# SparkFun_ESP8266_Thing_v10.net
KiCad netlist of a schematic drawn in EAGLE
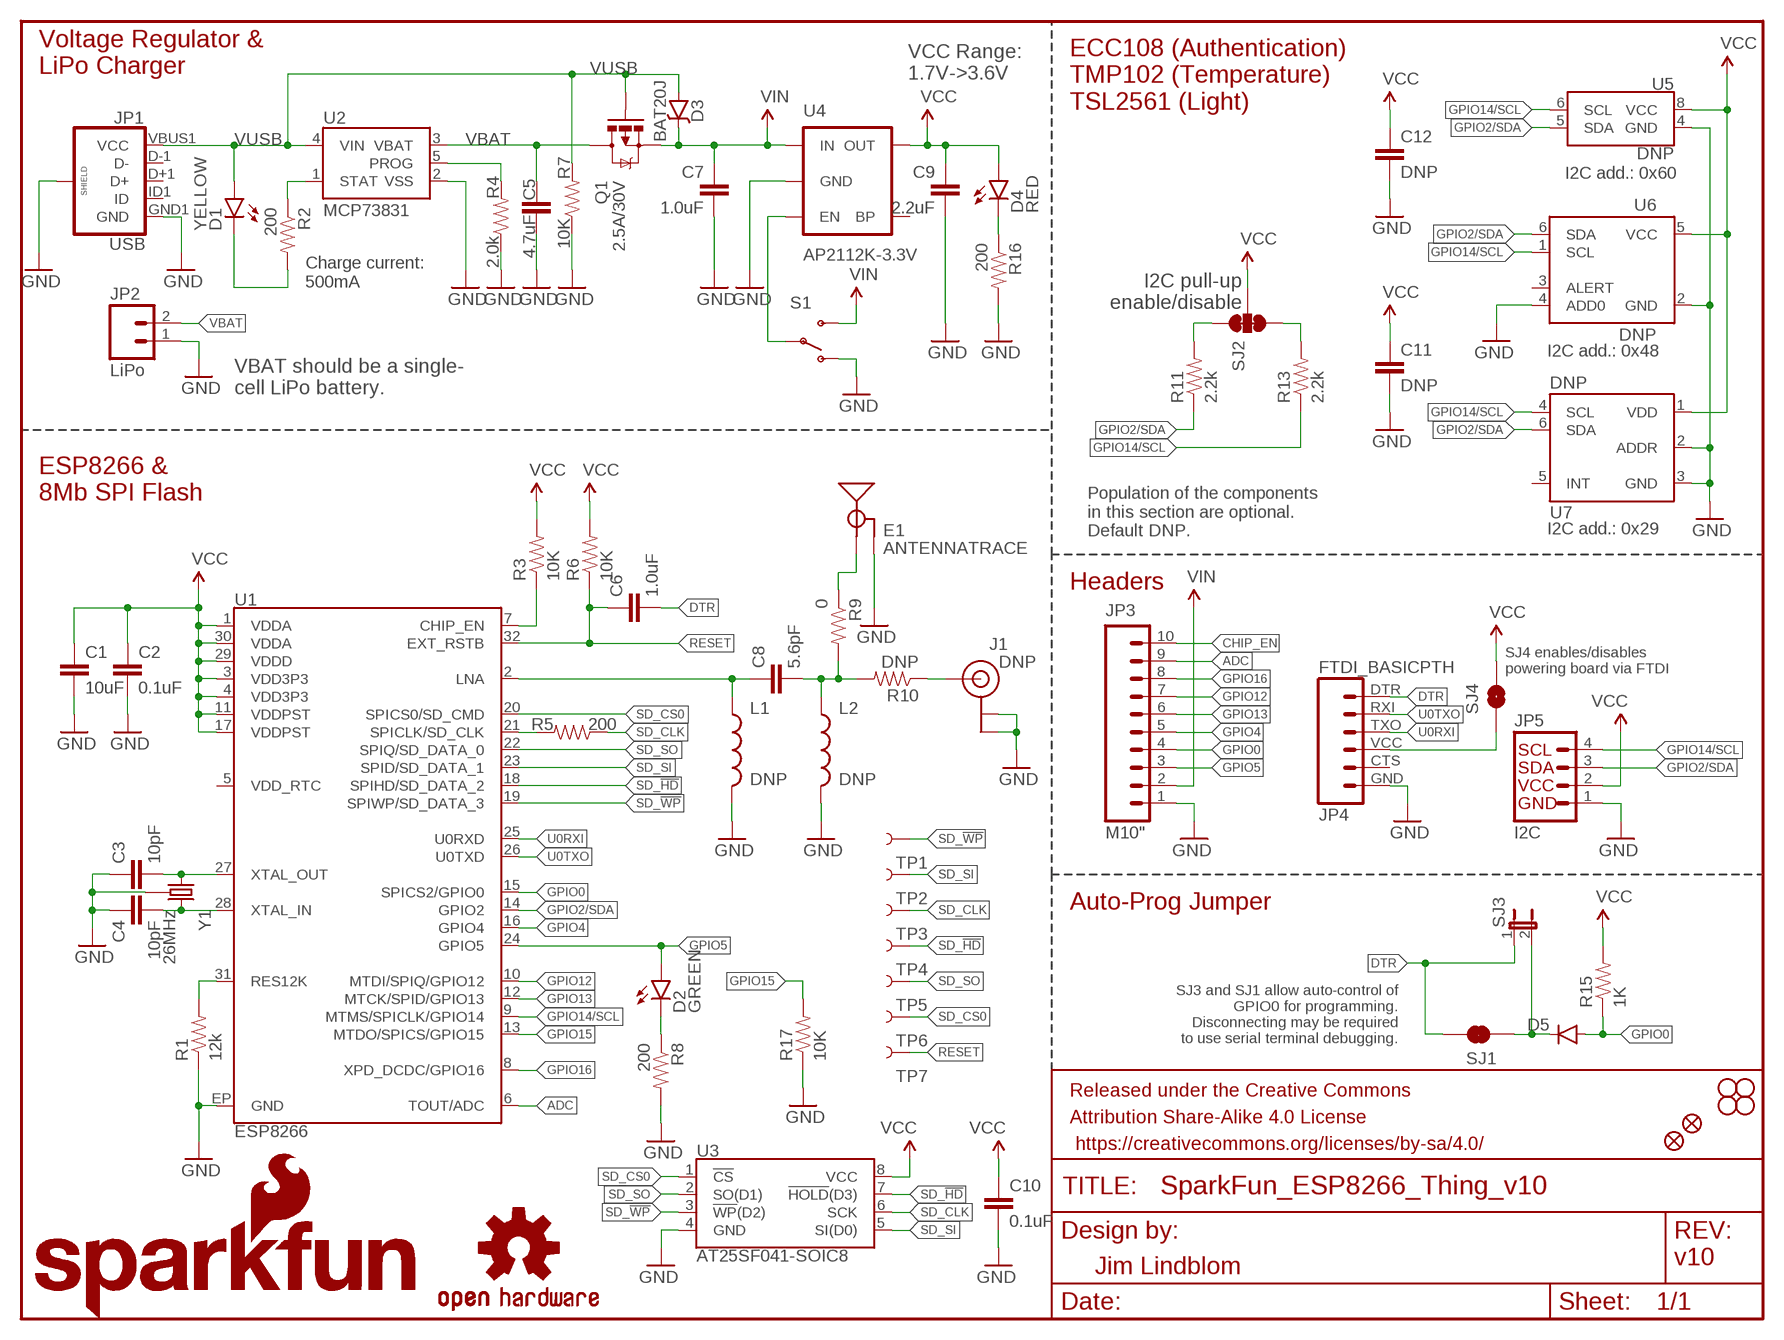
[diagram p0: schematic, sheet 1]

(export (version "E")
  (design (tool "Eeschema 10.0.6"))
  (components
    (comp (ref "C1")
      (value "10uF")
      (footprint "eagle-import:0603-CAP")
      (libsource (lib "eagle-import") (part "10UF-6.3V-20%(0603)"))
    )
    (comp (ref "C2")
      (value "0.1uF")
      (footprint "eagle-import:0603-CAP")
      (libsource (lib "eagle-import") (part "0.1UF-25V(+80/-20%)(0603)"))
    )
    (comp (ref "C3")
      (value "10pF")
      (footprint "eagle-import:0603-CAP")
      (libsource (lib "eagle-import") (part "10PF-50V-5%(0603)"))
    )
    (comp (ref "C4")
      (value "10pF")
      (footprint "eagle-import:0603-CAP")
      (libsource (lib "eagle-import") (part "10PF-50V-5%(0603)"))
    )
    (comp (ref "C5")
      (value "4.7uF")
      (footprint "eagle-import:0603-CAP")
      (libsource (lib "eagle-import") (part "4.7UF-6.3V-10%(0603)0603"))
    )
    (comp (ref "C6")
      (value "1.0uF")
      (footprint "eagle-import:0603-CAP")
      (libsource (lib "eagle-import") (part "1.0UF-16V-10%(0603)"))
    )
    (comp (ref "C7")
      (value "1.0uF")
      (footprint "eagle-import:0805")
      (libsource (lib "eagle-import") (part "1.0UF-25V-+80/-20(0805)"))
    )
    (comp (ref "C8")
      (value "5.6pF")
      (footprint "eagle-import:0603-CAP")
      (libsource (lib "eagle-import") (part "CAP0603-CAP"))
    )
    (comp (ref "C9")
      (value "2.2uF")
      (footprint "eagle-import:0603-CAP")
      (libsource (lib "eagle-import") (part "2.2UF-10V-20%(0603)"))
    )
    (comp (ref "C10")
      (value "0.1uF")
      (footprint "eagle-import:0603-CAP")
      (libsource (lib "eagle-import") (part "0.1UF-25V(+80/-20%)(0603)"))
    )
    (comp (ref "C11")
      (value "DNP")
      (footprint "eagle-import:0603-CAP")
      (libsource (lib "eagle-import") (part "0.1UF-25V(+80/-20%)(0603)"))
    )
    (comp (ref "C12")
      (value "DNP")
      (footprint "eagle-import:0603-CAP")
      (libsource (lib "eagle-import") (part "0.1UF-25V(+80/-20%)(0603)"))
    )
    (comp (ref "D1")
      (value "YELLOW")
      (footprint "eagle-import:LED-0603")
      (libsource (lib "eagle-import") (part "LED-YELLOW0603"))
    )
    (comp (ref "D2")
      (value "GREEN")
      (footprint "eagle-import:LED-0603")
      (libsource (lib "eagle-import") (part "LED-GREEN0603"))
    )
    (comp (ref "D3")
      (value "BAT20J")
      (footprint "eagle-import:SOD-323")
      (libsource (lib "eagle-import") (part "DIODE-SCHOTTKY-BAT20J"))
    )
    (comp (ref "D4")
      (value "RED")
      (footprint "eagle-import:LED-0603")
      (libsource (lib "eagle-import") (part "LED-RED0603"))
    )
    (comp (ref "D5")
      (value "DIODEBAS16")
      (footprint "eagle-import:SOD-323")
      (libsource (lib "eagle-import") (part "DIODEBAS16"))
    )
    (comp (ref "E1")
      (value "ANTENNATRACE")
      (footprint "eagle-import:TRACE_ANTENNA_2.4GHZ_25.7MM")
      (libsource (lib "eagle-import") (part "ANTENNATRACE"))
    )
    (comp (ref "FID1")
      (value "FIDUCIAL1X2")
      (footprint "eagle-import:FIDUCIAL-1X2")
      (libsource (lib "eagle-import") (part "FIDUCIAL1X2"))
    )
    (comp (ref "FID2")
      (value "FIDUCIAL1X2")
      (footprint "eagle-import:FIDUCIAL-1X2")
      (libsource (lib "eagle-import") (part "FIDUCIAL1X2"))
    )
    (comp (ref "FRAME1")
      (value "FRAME-LETTER")
      (footprint "eagle-import:CREATIVE_COMMONS")
      (libsource (lib "eagle-import") (part "FRAME-LETTER"))
    )
    (comp (ref "J1")
      (value "DNP")
      (footprint "eagle-import:U.FL")
      (libsource (lib "eagle-import") (part "U.FL"))
    )
    (comp (ref "JP1")
      (value "USB")
      (footprint "eagle-import:USB-B-MICRO-SMD_V03")
      (libsource (lib "eagle-import") (part "USB_MICROB_PLUGCONN-11752"))
    )
    (comp (ref "JP2")
      (value "LiPo")
      (footprint "eagle-import:JST-2-PTH")
      (libsource (lib "eagle-import") (part "M02JST-PTH-2"))
    )
    (comp (ref "JP3")
      (value "M10\"")
      (footprint "eagle-import:1X10")
      (libsource (lib "eagle-import") (part "M10{dblquote}"))
    )
    (comp (ref "JP4")
      (value "FTDI_BASICPTH")
      (footprint "eagle-import:FTDI_BASIC")
      (libsource (lib "eagle-import") (part "FTDI_BASICPTH"))
    )
    (comp (ref "JP5")
      (value "I2C")
      (footprint "eagle-import:1X04")
      (libsource (lib "eagle-import") (part "I2C_STANDARD"))
    )
    (comp (ref "L1")
      (value "DNP")
      (footprint "eagle-import:0603")
      (libsource (lib "eagle-import") (part "INDUCTOR0603"))
    )
    (comp (ref "L2")
      (value "DNP")
      (footprint "eagle-import:0603")
      (libsource (lib "eagle-import") (part "INDUCTOR0603"))
    )
    (comp (ref "LOGO1")
      (value "SFE_LOGO_NAME.2_INCH")
      (footprint "eagle-import:SFE_LOGO_NAME_.2")
      (libsource (lib "eagle-import") (part "SFE_LOGO_NAME.2_INCH"))
    )
    (comp (ref "LOGO3")
      (value "SFE_LOGO_FLAME.1_INCH")
      (footprint "eagle-import:SFE_LOGO_FLAME_.1")
      (libsource (lib "eagle-import") (part "SFE_LOGO_FLAME.1_INCH"))
    )
    (comp (ref "LOGO4")
      (value "OSHW-LOGOS")
      (footprint "eagle-import:OSHW-LOGO-S")
      (libsource (lib "eagle-import") (part "OSHW-LOGOS"))
    )
    (comp (ref "Q1")
      (value "2.5A/30V")
      (footprint "eagle-import:SOT23-3")
      (libsource (lib "eagle-import") (part "MOSFET-PCHANNELDMG2307L"))
    )
    (comp (ref "R1")
      (value "12k")
      (footprint "eagle-import:0603-RES")
      (libsource (lib "eagle-import") (part "12KOHM-1/10W-1%(0603)"))
    )
    (comp (ref "R2")
      (value "200")
      (footprint "eagle-import:0603-RES")
      (libsource (lib "eagle-import") (part "200OHM1/10W1%(0603)"))
    )
    (comp (ref "R3")
      (value "10K")
      (footprint "eagle-import:0603-RES")
      (libsource (lib "eagle-import") (part "10KOHM1/10W1%(0603)0603"))
    )
    (comp (ref "R4")
      (value "2.0k")
      (footprint "eagle-import:0603-RES")
      (libsource (lib "eagle-import") (part "2.0KOHM1/10W5%(0603)"))
    )
    (comp (ref "R5")
      (value "200")
      (footprint "eagle-import:0603-RES")
      (libsource (lib "eagle-import") (part "200OHM1/10W1%(0603)"))
    )
    (comp (ref "R6")
      (value "10K")
      (footprint "eagle-import:0603-RES")
      (libsource (lib "eagle-import") (part "10KOHM1/10W1%(0603)0603"))
    )
    (comp (ref "R7")
      (value "10K")
      (footprint "eagle-import:0603-RES")
      (libsource (lib "eagle-import") (part "10KOHM1/10W1%(0603)0603"))
    )
    (comp (ref "R8")
      (value "200")
      (footprint "eagle-import:0603-RES")
      (libsource (lib "eagle-import") (part "200OHM1/10W1%(0603)"))
    )
    (comp (ref "R9")
      (value "0")
      (footprint "eagle-import:0603")
      (libsource (lib "eagle-import") (part "0OHM1/10W5%(0603)"))
    )
    (comp (ref "R10")
      (value "DNP")
      (footprint "eagle-import:0603-RES")
      (libsource (lib "eagle-import") (part "RESISTOR0603-RES"))
    )
    (comp (ref "R11")
      (value "2.2k")
      (footprint "eagle-import:0603-RES")
      (libsource (lib "eagle-import") (part "2.2KOHM1/10W1%(0603)"))
    )
    (comp (ref "R13")
      (value "2.2k")
      (footprint "eagle-import:0603-RES")
      (libsource (lib "eagle-import") (part "2.2KOHM1/10W1%(0603)"))
    )
    (comp (ref "R15")
      (value "1K")
      (footprint "eagle-import:0603-RES")
      (libsource (lib "eagle-import") (part "1KOHM1/10W1%(0603)"))
    )
    (comp (ref "R16")
      (value "200")
      (footprint "eagle-import:0603-RES")
      (libsource (lib "eagle-import") (part "200OHM1/10W1%(0603)"))
    )
    (comp (ref "R17")
      (value "10K")
      (footprint "eagle-import:0603-RES")
      (libsource (lib "eagle-import") (part "10KOHM1/10W1%(0603)0603"))
    )
    (comp (ref "S1")
      (value "SWITCH-SPDT-SMD-A")
      (footprint "eagle-import:SWITCH-SPST-SMD-A")
      (libsource (lib "eagle-import") (part "SWITCH-SPDT-SMD-A"))
    )
    (comp (ref "SJ1")
      (value "JUMPER-PAD-2-NC_BY_TRACE")
      (footprint "eagle-import:PAD-JUMPER-2-NC_BY_TRACE_YES_SILK")
      (libsource (lib "eagle-import") (part "JUMPER-PAD-2-NC_BY_TRACE"))
    )
    (comp (ref "SJ2")
      (value "JUMPER-PAD-3-NC_BY_TRACE")
      (footprint "eagle-import:PAD-JUMPER-3-3OF3_NC_BY_TRACE_YES_SILK_FULL_BOX")
      (libsource (lib "eagle-import") (part "JUMPER-PAD-3-NC_BY_TRACE"))
    )
    (comp (ref "SJ3")
      (value "JUMPER-PTH-2-NC")
      (footprint "eagle-import:PTH-JUMPER-NC_BOTTOM_NO_SILK")
      (libsource (lib "eagle-import") (part "JUMPER-PTH-2-NC"))
    )
    (comp (ref "SJ4")
      (value "JUMPER-PAD-2-NOYES_SILK")
      (footprint "eagle-import:PAD-JUMPER-2-NO_YES_SILK")
      (libsource (lib "eagle-import") (part "JUMPER-PAD-2-NOYES_SILK"))
    )
    (comp (ref "STANDOFF1")
      (value "STAND-OFF")
      (footprint "eagle-import:STAND-OFF")
      (libsource (lib "eagle-import") (part "STAND-OFF"))
    )
    (comp (ref "STANDOFF2")
      (value "STAND-OFF")
      (footprint "eagle-import:STAND-OFF")
      (libsource (lib "eagle-import") (part "STAND-OFF"))
    )
    (comp (ref "STANDOFF3")
      (value "STAND-OFF")
      (footprint "eagle-import:STAND-OFF")
      (libsource (lib "eagle-import") (part "STAND-OFF"))
    )
    (comp (ref "STANDOFF4")
      (value "STAND-OFF")
      (footprint "eagle-import:STAND-OFF")
      (libsource (lib "eagle-import") (part "STAND-OFF"))
    )
    (comp (ref "TP1")
      (value "TEST-POINT3X5")
      (footprint "eagle-import:PAD.03X.05")
      (libsource (lib "eagle-import") (part "TEST-POINT3X5"))
    )
    (comp (ref "TP2")
      (value "TEST-POINT3X5")
      (footprint "eagle-import:PAD.03X.05")
      (libsource (lib "eagle-import") (part "TEST-POINT3X5"))
    )
    (comp (ref "TP3")
      (value "TEST-POINT3X5")
      (footprint "eagle-import:PAD.03X.05")
      (libsource (lib "eagle-import") (part "TEST-POINT3X5"))
    )
    (comp (ref "TP4")
      (value "TEST-POINT3X5")
      (footprint "eagle-import:PAD.03X.05")
      (libsource (lib "eagle-import") (part "TEST-POINT3X5"))
    )
    (comp (ref "TP5")
      (value "TEST-POINT3X5")
      (footprint "eagle-import:PAD.03X.05")
      (libsource (lib "eagle-import") (part "TEST-POINT3X5"))
    )
    (comp (ref "TP6")
      (value "TEST-POINT3X5")
      (footprint "eagle-import:PAD.03X.05")
      (libsource (lib "eagle-import") (part "TEST-POINT3X5"))
    )
    (comp (ref "TP7")
      (value "TEST-POINT3X5")
      (footprint "eagle-import:PAD.03X.05")
      (libsource (lib "eagle-import") (part "TEST-POINT3X5"))
    )
    (comp (ref "U1")
      (value "ESP8266")
      (footprint "eagle-import:QFN32")
      (libsource (lib "eagle-import") (part "ESP8266"))
    )
    (comp (ref "U2")
      (value "MCP73831")
      (footprint "eagle-import:SOT23-5")
      (libsource (lib "eagle-import") (part "MCP73831"))
    )
    (comp (ref "U3")
      (value "AT25SF041-SOIC8")
      (footprint "eagle-import:SO08")
      (libsource (lib "eagle-import") (part "AT25SF041-SOIC8"))
    )
    (comp (ref "U4")
      (value "AP2112K-3.3V")
      (footprint "eagle-import:SOT23-5")
      (libsource (lib "eagle-import") (part "V_REG_LDOSMD"))
    )
    (comp (ref "U5")
      (value "DNP")
      (footprint "eagle-import:UDFN8")
      (libsource (lib "eagle-import") (part "ATECC108-MAHDA"))
    )
    (comp (ref "U6")
      (value "DNP")
      (footprint "eagle-import:SOT563-2")
      (libsource (lib "eagle-import") (part "TMP1021{colon}1"))
    )
    (comp (ref "U7")
      (value "DNP")
      (footprint "eagle-import:FN-6")
      (libsource (lib "eagle-import") (part "TSL2561FN"))
    )
    (comp (ref "Y1")
      (value "26MHz")
      (footprint "eagle-import:CRYSTAL-SMD-3.2X2.5")
      (libsource (lib "eagle-import") (part "CRYSTAL-GROUNDED3.2X2.5"))
    )
  )
  (nets
    (net (code "1") (name "/SD_~{HD}") (class "Default")
      (node (ref "TP4") (pin "P$1") (pinfunction "1_P$1") (pintype "bidirectional"))
      (node (ref "U1") (pin "18") (pinfunction "SPIHD/SD_DATA_2_18") (pintype "bidirectional"))
      (node (ref "U3") (pin "7") (pinfunction "~{HOLD}(D3)_7") (pintype "bidirectional"))
    )
    (net (code "2") (name "/SD_~{WP}") (class "Default")
      (node (ref "TP1") (pin "P$1") (pinfunction "1_P$1") (pintype "bidirectional"))
      (node (ref "U1") (pin "19") (pinfunction "SPIWP/SD_DATA_3_19") (pintype "bidirectional"))
      (node (ref "U3") (pin "3") (pinfunction "~{WP}(D2)_3") (pintype "bidirectional"))
    )
    (net (code "3") (name "/VUSB") (class "Default")
      (node (ref "D1") (pin "A") (pinfunction "A_A") (pintype "passive"))
      (node (ref "D3") (pin "A") (pinfunction "A_A") (pintype "passive"))
      (node (ref "JP1") (pin "VBUS1") (pinfunction "VCC_VBUS1") (pintype "bidirectional"))
      (node (ref "Q1") (pin "1") (pinfunction "G_1") (pintype "passive"))
      (node (ref "R7") (pin "2") (pinfunction "2_2") (pintype "passive"))
      (node (ref "U2") (pin "4") (pinfunction "VIN_4") (pintype "power_in"))
    )
    (net (code "4") (name "ADC") (class "Default")
      (node (ref "JP3") (pin "9") (pinfunction "9_9") (pintype "passive"))
      (node (ref "U1") (pin "6") (pinfunction "TOUT/ADC_6") (pintype "bidirectional"))
    )
    (net (code "5") (name "CHIP_EN") (class "Default")
      (node (ref "JP3") (pin "10") (pinfunction "10_10") (pintype "passive"))
      (node (ref "R3") (pin "1") (pinfunction "1_1") (pintype "passive"))
      (node (ref "U1") (pin "7") (pinfunction "CHIP_EN_7") (pintype "bidirectional"))
    )
    (net (code "6") (name "DTR") (class "Default")
      (node (ref "C6") (pin "2") (pinfunction "2_2") (pintype "passive"))
      (node (ref "JP4") (pin "DTR") (pinfunction "1_DTR") (pintype "passive"))
      (node (ref "SJ1") (pin "2") (pinfunction "2_2") (pintype "passive"))
      (node (ref "SJ3") (pin "1") (pinfunction "1_1") (pintype "passive"))
    )
    (net (code "7") (name "GND") (class "Default")
      (node (ref "C1") (pin "2") (pinfunction "2_2") (pintype "passive"))
      (node (ref "C10") (pin "2") (pinfunction "2_2") (pintype "passive"))
      (node (ref "C11") (pin "2") (pinfunction "2_2") (pintype "passive"))
      (node (ref "C12") (pin "2") (pinfunction "2_2") (pintype "passive"))
      (node (ref "C2") (pin "2") (pinfunction "2_2") (pintype "passive"))
      (node (ref "C3") (pin "1") (pinfunction "1_1") (pintype "passive"))
      (node (ref "C4") (pin "1") (pinfunction "1_1") (pintype "passive"))
      (node (ref "C5") (pin "2") (pinfunction "2_2") (pintype "passive"))
      (node (ref "C7") (pin "2") (pinfunction "2_2") (pintype "passive"))
      (node (ref "C9") (pin "2") (pinfunction "2_2") (pintype "passive"))
      (node (ref "E1") (pin "GND") (pinfunction "GND_GND") (pintype "bidirectional"))
      (node (ref "E1") (pin "GND2") (pinfunction "GND_GND2") (pintype "bidirectional"))
      (node (ref "J1") (pin "P$1") (pinfunction "GND_P$1") (pintype "bidirectional"))
      (node (ref "J1") (pin "P$2") (pinfunction "GND_P$2") (pintype "bidirectional"))
      (node (ref "JP1") (pin "GND1") (pinfunction "GND_GND1") (pintype "bidirectional"))
      (node (ref "JP1") (pin "SHIELD1") (pinfunction "SHIELD_SHIELD1") (pintype "bidirectional"))
      (node (ref "JP1") (pin "SHIELD2") (pinfunction "SHIELD_SHIELD2") (pintype "bidirectional"))
      (node (ref "JP1") (pin "SHIELD3") (pinfunction "SHIELD_SHIELD3") (pintype "bidirectional"))
      (node (ref "JP2") (pin "1") (pinfunction "1_1") (pintype "passive"))
      (node (ref "JP3") (pin "1") (pinfunction "1_1") (pintype "passive"))
      (node (ref "JP4") (pin "GND") (pinfunction "6_GND") (pintype "passive"))
      (node (ref "JP5") (pin "1") (pinfunction "1_1") (pintype "passive"))
      (node (ref "L1") (pin "2") (pinfunction "2_2") (pintype "passive"))
      (node (ref "L2") (pin "2") (pinfunction "2_2") (pintype "passive"))
      (node (ref "R1") (pin "1") (pinfunction "1_1") (pintype "passive"))
      (node (ref "R16") (pin "2") (pinfunction "2_2") (pintype "passive"))
      (node (ref "R17") (pin "1") (pinfunction "1_1") (pintype "passive"))
      (node (ref "R4") (pin "1") (pinfunction "1_1") (pintype "passive"))
      (node (ref "R7") (pin "1") (pinfunction "1_1") (pintype "passive"))
      (node (ref "R8") (pin "2") (pinfunction "2_2") (pintype "passive"))
      (node (ref "S1") (pin "1") (pinfunction "O_1") (pintype "passive"))
      (node (ref "U1") (pin "EP") (pinfunction "GND_EP") (pintype "bidirectional"))
      (node (ref "U2") (pin "2") (pinfunction "VSS_2") (pintype "power_in"))
      (node (ref "U3") (pin "4") (pinfunction "GND_4") (pintype "bidirectional"))
      (node (ref "U4") (pin "2") (pinfunction "GND_2") (pintype "input"))
      (node (ref "U5") (pin "4") (pinfunction "GND_4") (pintype "bidirectional"))
      (node (ref "U6") (pin "2") (pinfunction "GND_2") (pintype "bidirectional"))
      (node (ref "U6") (pin "4") (pinfunction "ADD0_4") (pintype "bidirectional"))
      (node (ref "U7") (pin "2") (pinfunction "ADDR_2") (pintype "input"))
      (node (ref "U7") (pin "3") (pinfunction "GND_3") (pintype "power_in"))
      (node (ref "Y1") (pin "2") (pinfunction "GND_2") (pintype "passive"))
      (node (ref "Y1") (pin "4") (pinfunction "GND_4") (pintype "passive"))
    )
    (net (code "8") (name "GPIO0") (class "Default")
      (node (ref "D5") (pin "A") (pinfunction "A_A") (pintype "passive"))
      (node (ref "JP3") (pin "4") (pinfunction "4_4") (pintype "passive"))
      (node (ref "R15") (pin "1") (pinfunction "1_1") (pintype "passive"))
      (node (ref "U1") (pin "15") (pinfunction "SPICS2/GPIO0_15") (pintype "bidirectional"))
    )
    (net (code "9") (name "GPIO2{slash}SDA") (class "Default")
      (node (ref "JP5") (pin "3") (pinfunction "3_3") (pintype "passive"))
      (node (ref "R11") (pin "1") (pinfunction "1_1") (pintype "passive"))
      (node (ref "U1") (pin "14") (pinfunction "GPIO2_14") (pintype "bidirectional"))
      (node (ref "U5") (pin "5") (pinfunction "SDA_5") (pintype "bidirectional"))
      (node (ref "U6") (pin "6") (pinfunction "SDA_6") (pintype "bidirectional"))
      (node (ref "U7") (pin "6") (pinfunction "SDA_6") (pintype "bidirectional"))
    )
    (net (code "10") (name "GPIO4") (class "Default")
      (node (ref "JP3") (pin "5") (pinfunction "5_5") (pintype "passive"))
      (node (ref "U1") (pin "16") (pinfunction "GPIO4_16") (pintype "bidirectional"))
    )
    (net (code "11") (name "GPIO5") (class "Default")
      (node (ref "D2") (pin "A") (pinfunction "A_A") (pintype "passive"))
      (node (ref "JP3") (pin "3") (pinfunction "3_3") (pintype "passive"))
      (node (ref "U1") (pin "24") (pinfunction "GPIO5_24") (pintype "bidirectional"))
    )
    (net (code "12") (name "GPIO12") (class "Default")
      (node (ref "JP3") (pin "7") (pinfunction "7_7") (pintype "passive"))
      (node (ref "U1") (pin "10") (pinfunction "MTDI/SPIQ/GPIO12_10") (pintype "bidirectional"))
    )
    (net (code "13") (name "GPIO13") (class "Default")
      (node (ref "JP3") (pin "6") (pinfunction "6_6") (pintype "passive"))
      (node (ref "U1") (pin "12") (pinfunction "MTCK/SPID/GPIO13_12") (pintype "bidirectional"))
    )
    (net (code "14") (name "GPIO14{slash}SCL") (class "Default")
      (node (ref "JP5") (pin "4") (pinfunction "4_4") (pintype "passive"))
      (node (ref "R13") (pin "1") (pinfunction "1_1") (pintype "passive"))
      (node (ref "U1") (pin "9") (pinfunction "MTMS/SPICLK/GPIO14_9") (pintype "bidirectional"))
      (node (ref "U5") (pin "6") (pinfunction "SCL_6") (pintype "bidirectional"))
      (node (ref "U6") (pin "1") (pinfunction "SCL_1") (pintype "bidirectional"))
      (node (ref "U7") (pin "4") (pinfunction "SCL_4") (pintype "input"))
    )
    (net (code "15") (name "GPIO15") (class "Default")
      (node (ref "R17") (pin "2") (pinfunction "2_2") (pintype "passive"))
      (node (ref "U1") (pin "13") (pinfunction "MTDO/SPICS/GPIO15_13") (pintype "bidirectional"))
    )
    (net (code "16") (name "GPIO16") (class "Default")
      (node (ref "JP3") (pin "8") (pinfunction "8_8") (pintype "passive"))
      (node (ref "U1") (pin "8") (pinfunction "XPD_DCDC/GPIO16_8") (pintype "bidirectional"))
    )
    (net (code "17") (name "Net-(C8-Pad2)") (class "Default")
      (node (ref "C8") (pin "2") (pinfunction "2_2") (pintype "passive"))
      (node (ref "L2") (pin "1") (pinfunction "1_1") (pintype "passive"))
      (node (ref "R10") (pin "2") (pinfunction "2_2") (pintype "passive"))
      (node (ref "R9") (pin "2") (pinfunction "2_2") (pintype "passive"))
    )
    (net (code "18") (name "Net-(D1-PadC)") (class "Default")
      (node (ref "D1") (pin "C") (pinfunction "C_C") (pintype "passive"))
      (node (ref "R2") (pin "2") (pinfunction "2_2") (pintype "passive"))
    )
    (net (code "19") (name "Net-(D2-PadC)") (class "Default")
      (node (ref "D2") (pin "C") (pinfunction "C_C") (pintype "passive"))
      (node (ref "R8") (pin "1") (pinfunction "1_1") (pintype "passive"))
    )
    (net (code "20") (name "Net-(D4-PadC)") (class "Default")
      (node (ref "D4") (pin "C") (pinfunction "C_C") (pintype "passive"))
      (node (ref "R16") (pin "1") (pinfunction "1_1") (pintype "passive"))
    )
    (net (code "21") (name "Net-(D5-PadC)") (class "Default")
      (node (ref "D5") (pin "C") (pinfunction "C_C") (pintype "passive"))
      (node (ref "SJ1") (pin "1") (pinfunction "1_1") (pintype "passive"))
      (node (ref "SJ3") (pin "2") (pinfunction "2_2") (pintype "passive"))
    )
    (net (code "22") (name "Net-(E1-SIGNAL)") (class "Default")
      (node (ref "E1") (pin "ANT") (pinfunction "SIGNAL_ANT") (pintype "bidirectional"))
      (node (ref "R9") (pin "1") (pinfunction "1_1") (pintype "passive"))
    )
    (net (code "23") (name "Net-(J1-SIGNAL)") (class "Default")
      (node (ref "J1") (pin "P$3") (pinfunction "SIGNAL_P$3") (pintype "bidirectional"))
      (node (ref "R10") (pin "1") (pinfunction "1_1") (pintype "passive"))
    )
    (net (code "24") (name "Net-(JP4-4)") (class "Default")
      (node (ref "JP4") (pin "VCC") (pinfunction "4_VCC") (pintype "passive"))
      (node (ref "SJ4") (pin "1") (pinfunction "1_1") (pintype "passive"))
    )
    (net (code "25") (name "Net-(R11-Pad2)") (class "Default")
      (node (ref "R11") (pin "2") (pinfunction "2_2") (pintype "passive"))
      (node (ref "SJ2") (pin "1") (pinfunction "1_1") (pintype "passive"))
    )
    (net (code "26") (name "Net-(R13-Pad2)") (class "Default")
      (node (ref "R13") (pin "2") (pinfunction "2_2") (pintype "passive"))
      (node (ref "SJ2") (pin "3") (pinfunction "3_3") (pintype "passive"))
    )
    (net (code "27") (name "Net-(S1-P)") (class "Default")
      (node (ref "S1") (pin "2") (pinfunction "P_2") (pintype "passive"))
      (node (ref "U4") (pin "3") (pinfunction "EN_3") (pintype "input"))
    )
    (net (code "28") (name "Net-(U1-LNA)") (class "Default")
      (node (ref "C8") (pin "1") (pinfunction "1_1") (pintype "passive"))
      (node (ref "L1") (pin "1") (pinfunction "1_1") (pintype "passive"))
      (node (ref "U1") (pin "2") (pinfunction "LNA_2") (pintype "bidirectional"))
    )
    (net (code "29") (name "Net-(U1-RES12K)") (class "Default")
      (node (ref "R1") (pin "2") (pinfunction "2_2") (pintype "passive"))
      (node (ref "U1") (pin "31") (pinfunction "RES12K_31") (pintype "bidirectional"))
    )
    (net (code "30") (name "Net-(U1-SPICLK{slash}SD_CLK)") (class "Default")
      (node (ref "R5") (pin "2") (pinfunction "2_2") (pintype "passive"))
      (node (ref "U1") (pin "21") (pinfunction "SPICLK/SD_CLK_21") (pintype "bidirectional"))
    )
    (net (code "31") (name "Net-(U1-XTAL_IN)") (class "Default")
      (node (ref "C4") (pin "2") (pinfunction "2_2") (pintype "passive"))
      (node (ref "U1") (pin "28") (pinfunction "XTAL_IN_28") (pintype "bidirectional"))
      (node (ref "Y1") (pin "3") (pinfunction "2_3") (pintype "passive"))
    )
    (net (code "32") (name "Net-(U1-XTAL_OUT)") (class "Default")
      (node (ref "C3") (pin "2") (pinfunction "2_2") (pintype "passive"))
      (node (ref "U1") (pin "27") (pinfunction "XTAL_OUT_27") (pintype "bidirectional"))
      (node (ref "Y1") (pin "1") (pinfunction "1_1") (pintype "passive"))
    )
    (net (code "33") (name "Net-(U2-PROG)") (class "Default")
      (node (ref "R4") (pin "2") (pinfunction "2_2") (pintype "passive"))
      (node (ref "U2") (pin "5") (pinfunction "PROG_5") (pintype "input"))
    )
    (net (code "34") (name "Net-(U2-STAT)") (class "Default")
      (node (ref "R2") (pin "1") (pinfunction "1_1") (pintype "passive"))
      (node (ref "U2") (pin "1") (pinfunction "STAT_1") (pintype "output"))
    )
    (net (code "35") (name "RESET") (class "Default")
      (node (ref "C6") (pin "1") (pinfunction "1_1") (pintype "passive"))
      (node (ref "R6") (pin "1") (pinfunction "1_1") (pintype "passive"))
      (node (ref "TP7") (pin "P$1") (pinfunction "1_P$1") (pintype "bidirectional"))
      (node (ref "U1") (pin "32") (pinfunction "EXT_RSTB_32") (pintype "bidirectional"))
    )
    (net (code "36") (name "SD_CLK") (class "Default")
      (node (ref "R5") (pin "1") (pinfunction "1_1") (pintype "passive"))
      (node (ref "TP3") (pin "P$1") (pinfunction "1_P$1") (pintype "bidirectional"))
      (node (ref "U3") (pin "6") (pinfunction "SCK_6") (pintype "bidirectional"))
    )
    (net (code "37") (name "SD_CS0") (class "Default")
      (node (ref "TP6") (pin "P$1") (pinfunction "1_P$1") (pintype "bidirectional"))
      (node (ref "U1") (pin "20") (pinfunction "SPICS0/SD_CMD_20") (pintype "bidirectional"))
      (node (ref "U3") (pin "1") (pinfunction "~{CS}_1") (pintype "bidirectional"))
    )
    (net (code "38") (name "SD_SI") (class "Default")
      (node (ref "TP2") (pin "P$1") (pinfunction "1_P$1") (pintype "bidirectional"))
      (node (ref "U1") (pin "23") (pinfunction "SPID/SD_DATA_1_23") (pintype "bidirectional"))
      (node (ref "U3") (pin "5") (pinfunction "SI(D0)_5") (pintype "bidirectional"))
    )
    (net (code "39") (name "SD_SO") (class "Default")
      (node (ref "TP5") (pin "P$1") (pinfunction "1_P$1") (pintype "bidirectional"))
      (node (ref "U1") (pin "22") (pinfunction "SPIQ/SD_DATA_0_22") (pintype "bidirectional"))
      (node (ref "U3") (pin "2") (pinfunction "SO(D1)_2") (pintype "bidirectional"))
    )
    (net (code "40") (name "U0RXI") (class "Default")
      (node (ref "JP4") (pin "TXO") (pinfunction "3_TXO") (pintype "passive"))
      (node (ref "U1") (pin "25") (pinfunction "U0RXD_25") (pintype "bidirectional"))
    )
    (net (code "41") (name "U0TXO") (class "Default")
      (node (ref "JP4") (pin "RXI") (pinfunction "2_RXI") (pintype "passive"))
      (node (ref "U1") (pin "26") (pinfunction "U0TXD_26") (pintype "bidirectional"))
    )
    (net (code "42") (name "VBAT") (class "Default")
      (node (ref "C5") (pin "1") (pinfunction "1_1") (pintype "passive"))
      (node (ref "JP2") (pin "2") (pinfunction "2_2") (pintype "passive"))
      (node (ref "Q1") (pin "3") (pinfunction "D_3") (pintype "passive"))
      (node (ref "U2") (pin "3") (pinfunction "VBAT_3") (pintype "power_in"))
    )
    (net (code "43") (name "VCC") (class "Default")
      (node (ref "C1") (pin "1") (pinfunction "1_1") (pintype "passive"))
      (node (ref "C10") (pin "1") (pinfunction "1_1") (pintype "passive"))
      (node (ref "C11") (pin "1") (pinfunction "1_1") (pintype "passive"))
      (node (ref "C12") (pin "1") (pinfunction "1_1") (pintype "passive"))
      (node (ref "C2") (pin "1") (pinfunction "1_1") (pintype "passive"))
      (node (ref "C9") (pin "1") (pinfunction "1_1") (pintype "passive"))
      (node (ref "D4") (pin "A") (pinfunction "A_A") (pintype "passive"))
      (node (ref "JP5") (pin "2") (pinfunction "2_2") (pintype "passive"))
      (node (ref "R15") (pin "2") (pinfunction "2_2") (pintype "passive"))
      (node (ref "R3") (pin "2") (pinfunction "2_2") (pintype "passive"))
      (node (ref "R6") (pin "2") (pinfunction "2_2") (pintype "passive"))
      (node (ref "SJ2") (pin "2") (pinfunction "2_2") (pintype "passive"))
      (node (ref "SJ4") (pin "2") (pinfunction "2_2") (pintype "passive"))
      (node (ref "U1") (pin "1") (pinfunction "VDDA_1") (pintype "bidirectional"))
      (node (ref "U1") (pin "11") (pinfunction "VDDPST_11") (pintype "bidirectional"))
      (node (ref "U1") (pin "17") (pinfunction "VDDPST_17") (pintype "bidirectional"))
      (node (ref "U1") (pin "29") (pinfunction "VDDD_29") (pintype "bidirectional"))
      (node (ref "U1") (pin "3") (pinfunction "VDD3P3_3") (pintype "bidirectional"))
      (node (ref "U1") (pin "30") (pinfunction "VDDA_30") (pintype "bidirectional"))
      (node (ref "U1") (pin "4") (pinfunction "VDD3P3_4") (pintype "bidirectional"))
      (node (ref "U3") (pin "8") (pinfunction "VCC_8") (pintype "bidirectional"))
      (node (ref "U4") (pin "5") (pinfunction "OUT_5") (pintype "passive"))
      (node (ref "U5") (pin "8") (pinfunction "VCC_8") (pintype "bidirectional"))
      (node (ref "U6") (pin "5") (pinfunction "VCC_5") (pintype "bidirectional"))
      (node (ref "U7") (pin "1") (pinfunction "VDD_1") (pintype "power_in"))
    )
    (net (code "44") (name "VIN") (class "Default")
      (node (ref "C7") (pin "1") (pinfunction "1_1") (pintype "passive"))
      (node (ref "D3") (pin "C") (pinfunction "C_C") (pintype "passive"))
      (node (ref "JP3") (pin "2") (pinfunction "2_2") (pintype "passive"))
      (node (ref "Q1") (pin "2") (pinfunction "S_2") (pintype "passive"))
      (node (ref "S1") (pin "3") (pinfunction "S_3") (pintype "passive"))
      (node (ref "U4") (pin "1") (pinfunction "IN_1") (pintype "input"))
    )
    (net (code "45") (name "unconnected-(JP1-D+-PadD+1)") (class "Default")
      (node (ref "JP1") (pin "D+1") (pinfunction "D+_D+1") (pintype "bidirectional"))
    )
    (net (code "46") (name "unconnected-(JP1-D--PadD-1)") (class "Default")
      (node (ref "JP1") (pin "D-1") (pinfunction "D-_D-1") (pintype "bidirectional"))
    )
    (net (code "47") (name "unconnected-(JP1-ID-PadID1)") (class "Default")
      (node (ref "JP1") (pin "ID1") (pinfunction "ID_ID1") (pintype "bidirectional"))
    )
    (net (code "48") (name "unconnected-(JP4-5-PadCTS)") (class "Default")
      (node (ref "JP4") (pin "CTS") (pinfunction "5_CTS") (pintype "passive"))
    )
    (net (code "49") (name "unconnected-(U1-VDD_RTC-Pad5)") (class "Default")
      (node (ref "U1") (pin "5") (pinfunction "VDD_RTC_5") (pintype "bidirectional"))
    )
    (net (code "50") (name "unconnected-(U4-BP-Pad4)") (class "Default")
      (node (ref "U4") (pin "4") (pinfunction "BP_4") (pintype "input"))
    )
    (net (code "51") (name "unconnected-(U6-ALERT-Pad3)") (class "Default")
      (node (ref "U6") (pin "3") (pinfunction "ALERT_3") (pintype "bidirectional"))
    )
    (net (code "52") (name "unconnected-(U7-INT-Pad5)") (class "Default")
      (node (ref "U7") (pin "5") (pinfunction "INT_5") (pintype "output"))
    )
  )
)
